# gatorBytes_LED_board.net
KiCad netlist of a schematic drawn in EAGLE
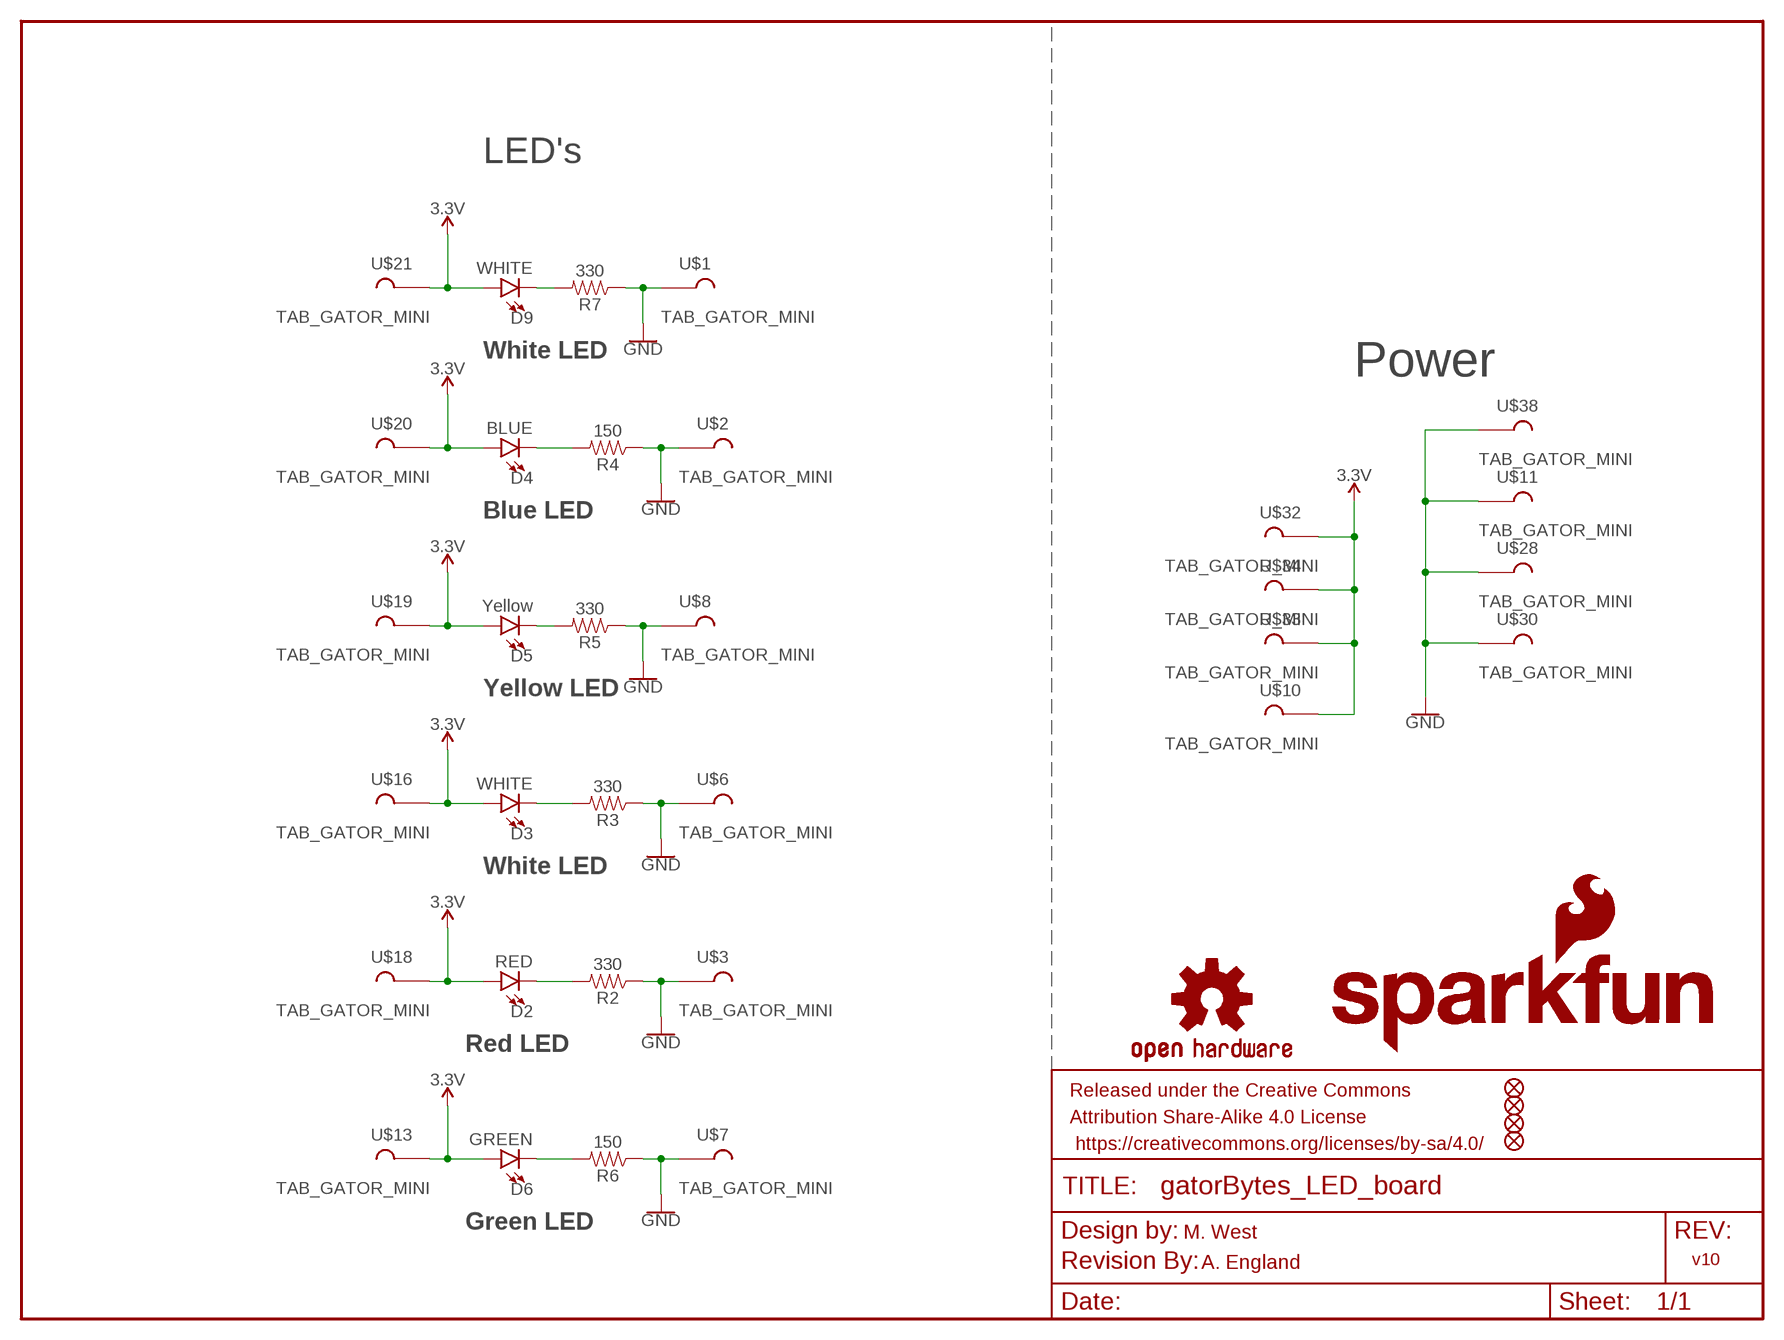
[diagram p0: schematic, sheet 1]

(export (version "E")
  (design (tool "Eeschema 10.0.6"))
  (components
    (comp (ref "D2")
      (value "RED")
      (footprint "eagle-import:LED-1206")
      (libsource (lib "eagle-import") (part "LED-RED1206"))
    )
    (comp (ref "D3")
      (value "WHITE")
      (footprint "eagle-import:LED-1206")
      (libsource (lib "eagle-import") (part "LED-WHITE1206"))
    )
    (comp (ref "D4")
      (value "BLUE")
      (footprint "eagle-import:LED-1206")
      (libsource (lib "eagle-import") (part "LED-BLUE1206"))
    )
    (comp (ref "D5")
      (value "Yellow")
      (footprint "eagle-import:LED-1206")
      (libsource (lib "eagle-import") (part "LED-YELLOWLILYPAD"))
    )
    (comp (ref "D6")
      (value "GREEN")
      (footprint "eagle-import:LED-1206")
      (libsource (lib "eagle-import") (part "LED-GREEN1206"))
    )
    (comp (ref "D9")
      (value "WHITE")
      (footprint "eagle-import:LED-1206")
      (libsource (lib "eagle-import") (part "LED-WHITE1206"))
    )
    (comp (ref "FD1")
      (value "FIDUCIALUFIDUCIAL")
      (footprint "eagle-import:FIDUCIAL-MICRO")
      (libsource (lib "eagle-import") (part "FIDUCIALUFIDUCIAL"))
    )
    (comp (ref "FD2")
      (value "FIDUCIALUFIDUCIAL")
      (footprint "eagle-import:FIDUCIAL-MICRO")
      (libsource (lib "eagle-import") (part "FIDUCIALUFIDUCIAL"))
    )
    (comp (ref "FD3")
      (value "FIDUCIALUFIDUCIAL")
      (footprint "eagle-import:FIDUCIAL-MICRO")
      (libsource (lib "eagle-import") (part "FIDUCIALUFIDUCIAL"))
    )
    (comp (ref "FD4")
      (value "FIDUCIALUFIDUCIAL")
      (footprint "eagle-import:FIDUCIAL-MICRO")
      (libsource (lib "eagle-import") (part "FIDUCIALUFIDUCIAL"))
    )
    (comp (ref "FRAME1")
      (value "FRAME-LETTER")
      (footprint "eagle-import:CREATIVE_COMMONS")
      (libsource (lib "eagle-import") (part "FRAME-LETTER"))
    )
    (comp (ref "LOGO1")
      (value "SFE_LOGO_FLAME.1_INCH")
      (footprint "eagle-import:SFE_LOGO_FLAME_.1")
      (libsource (lib "eagle-import") (part "SFE_LOGO_FLAME.1_INCH"))
    )
    (comp (ref "LOGO2")
      (value "OSHW-LOGOMINI")
      (footprint "eagle-import:OSHW-LOGO-MINI")
      (libsource (lib "eagle-import") (part "OSHW-LOGOMINI"))
    )
    (comp (ref "LOGO8")
      (value "REVISION")
      (footprint "eagle-import:REVISION")
      (libsource (lib "eagle-import") (part "REVISION"))
    )
    (comp (ref "LOGO15")
      (value "OSHW-LOGOMINI")
      (footprint "eagle-import:OSHW-LOGO-MINI")
      (libsource (lib "eagle-import") (part "OSHW-LOGOMINI"))
    )
    (comp (ref "LOGO16")
      (value "SFE_LOGO_NAME.1_INCH")
      (footprint "eagle-import:SFE_LOGO_NAME_.1")
      (libsource (lib "eagle-import") (part "SFE_LOGO_NAME.1_INCH"))
    )
    (comp (ref "R2")
      (value "330")
      (footprint "eagle-import:0603")
      (libsource (lib "eagle-import") (part "330OHM-0603-1/10W-1%"))
    )
    (comp (ref "R3")
      (value "330")
      (footprint "eagle-import:0603")
      (libsource (lib "eagle-import") (part "330OHM-0603-1/10W-1%"))
    )
    (comp (ref "R4")
      (value "150")
      (footprint "eagle-import:0603")
      (libsource (lib "eagle-import") (part "150OHM-0603-1/10W-1%"))
    )
    (comp (ref "R5")
      (value "330")
      (footprint "eagle-import:0603")
      (libsource (lib "eagle-import") (part "330OHM-0603-1/10W-1%"))
    )
    (comp (ref "R6")
      (value "150")
      (footprint "eagle-import:0603")
      (libsource (lib "eagle-import") (part "150OHM-0603-1/10W-1%"))
    )
    (comp (ref "R7")
      (value "330")
      (footprint "eagle-import:0603")
      (libsource (lib "eagle-import") (part "330OHM-0603-1/10W-1%"))
    )
    (comp (ref "U$1")
      (value "TAB_GATOR_MINI")
      (footprint "eagle-import:TAB_GATOR_MINI")
      (libsource (lib "eagle-import") (part "TAB_GATOR_MINI"))
    )
    (comp (ref "U$2")
      (value "TAB_GATOR_MINI")
      (footprint "eagle-import:TAB_GATOR_MINI")
      (libsource (lib "eagle-import") (part "TAB_GATOR_MINI"))
    )
    (comp (ref "U$3")
      (value "TAB_GATOR_MINI")
      (footprint "eagle-import:TAB_GATOR_MINI")
      (libsource (lib "eagle-import") (part "TAB_GATOR_MINI"))
    )
    (comp (ref "U$6")
      (value "TAB_GATOR_MINI")
      (footprint "eagle-import:TAB_GATOR_MINI")
      (libsource (lib "eagle-import") (part "TAB_GATOR_MINI"))
    )
    (comp (ref "U$7")
      (value "TAB_GATOR_MINI")
      (footprint "eagle-import:TAB_GATOR_MINI")
      (libsource (lib "eagle-import") (part "TAB_GATOR_MINI"))
    )
    (comp (ref "U$8")
      (value "TAB_GATOR_MINI")
      (footprint "eagle-import:TAB_GATOR_MINI")
      (libsource (lib "eagle-import") (part "TAB_GATOR_MINI"))
    )
    (comp (ref "U$10")
      (value "TAB_GATOR_MINI")
      (footprint "eagle-import:TAB_GATOR_MINI")
      (libsource (lib "eagle-import") (part "TAB_GATOR_MINI"))
    )
    (comp (ref "U$11")
      (value "TAB_GATOR_MINI")
      (footprint "eagle-import:TAB_GATOR_MINI")
      (libsource (lib "eagle-import") (part "TAB_GATOR_MINI"))
    )
    (comp (ref "U$13")
      (value "TAB_GATOR_MINI")
      (footprint "eagle-import:TAB_GATOR_MINI")
      (libsource (lib "eagle-import") (part "TAB_GATOR_MINI"))
    )
    (comp (ref "U$16")
      (value "TAB_GATOR_MINI")
      (footprint "eagle-import:TAB_GATOR_MINI")
      (libsource (lib "eagle-import") (part "TAB_GATOR_MINI"))
    )
    (comp (ref "U$18")
      (value "TAB_GATOR_MINI")
      (footprint "eagle-import:TAB_GATOR_MINI")
      (libsource (lib "eagle-import") (part "TAB_GATOR_MINI"))
    )
    (comp (ref "U$19")
      (value "TAB_GATOR_MINI")
      (footprint "eagle-import:TAB_GATOR_MINI")
      (libsource (lib "eagle-import") (part "TAB_GATOR_MINI"))
    )
    (comp (ref "U$20")
      (value "TAB_GATOR_MINI")
      (footprint "eagle-import:TAB_GATOR_MINI")
      (libsource (lib "eagle-import") (part "TAB_GATOR_MINI"))
    )
    (comp (ref "U$21")
      (value "TAB_GATOR_MINI")
      (footprint "eagle-import:TAB_GATOR_MINI")
      (libsource (lib "eagle-import") (part "TAB_GATOR_MINI"))
    )
    (comp (ref "U$28")
      (value "TAB_GATOR_MINI")
      (footprint "eagle-import:TAB_GATOR_MINI")
      (libsource (lib "eagle-import") (part "TAB_GATOR_MINI"))
    )
    (comp (ref "U$30")
      (value "TAB_GATOR_MINI")
      (footprint "eagle-import:TAB_GATOR_MINI")
      (libsource (lib "eagle-import") (part "TAB_GATOR_MINI"))
    )
    (comp (ref "U$32")
      (value "TAB_GATOR_MINI")
      (footprint "eagle-import:TAB_GATOR_MINI")
      (libsource (lib "eagle-import") (part "TAB_GATOR_MINI"))
    )
    (comp (ref "U$33")
      (value "TAB_GATOR_MINI")
      (footprint "eagle-import:TAB_GATOR_MINI")
      (libsource (lib "eagle-import") (part "TAB_GATOR_MINI"))
    )
    (comp (ref "U$34")
      (value "TAB_GATOR_MINI")
      (footprint "eagle-import:TAB_GATOR_MINI")
      (libsource (lib "eagle-import") (part "TAB_GATOR_MINI"))
    )
    (comp (ref "U$38")
      (value "TAB_GATOR_MINI")
      (footprint "eagle-import:TAB_GATOR_MINI")
      (libsource (lib "eagle-import") (part "TAB_GATOR_MINI"))
    )
  )
  (nets
    (net (code "1") (name "3.3V") (class "Default")
      (node (ref "D2") (pin "A") (pinfunction "A_A") (pintype "passive"))
      (node (ref "D3") (pin "A") (pinfunction "A_A") (pintype "passive"))
      (node (ref "D4") (pin "A") (pinfunction "A_A") (pintype "passive"))
      (node (ref "D5") (pin "A") (pinfunction "A_A") (pintype "passive"))
      (node (ref "D6") (pin "A") (pinfunction "A_A") (pintype "passive"))
      (node (ref "D9") (pin "A") (pinfunction "A_A") (pintype "passive"))
      (node (ref "U$10") (pin "P1") (pinfunction "P$1_P1") (pintype "bidirectional"))
      (node (ref "U$13") (pin "P1") (pinfunction "P$1_P1") (pintype "bidirectional"))
      (node (ref "U$16") (pin "P1") (pinfunction "P$1_P1") (pintype "bidirectional"))
      (node (ref "U$18") (pin "P1") (pinfunction "P$1_P1") (pintype "bidirectional"))
      (node (ref "U$19") (pin "P1") (pinfunction "P$1_P1") (pintype "bidirectional"))
      (node (ref "U$20") (pin "P1") (pinfunction "P$1_P1") (pintype "bidirectional"))
      (node (ref "U$21") (pin "P1") (pinfunction "P$1_P1") (pintype "bidirectional"))
      (node (ref "U$32") (pin "P1") (pinfunction "P$1_P1") (pintype "bidirectional"))
      (node (ref "U$33") (pin "P1") (pinfunction "P$1_P1") (pintype "bidirectional"))
      (node (ref "U$34") (pin "P1") (pinfunction "P$1_P1") (pintype "bidirectional"))
    )
    (net (code "2") (name "GND") (class "Default")
      (node (ref "R2") (pin "1") (pinfunction "1_1") (pintype "passive"))
      (node (ref "R3") (pin "1") (pinfunction "1_1") (pintype "passive"))
      (node (ref "R4") (pin "1") (pinfunction "1_1") (pintype "passive"))
      (node (ref "R5") (pin "1") (pinfunction "1_1") (pintype "passive"))
      (node (ref "R6") (pin "1") (pinfunction "1_1") (pintype "passive"))
      (node (ref "R7") (pin "1") (pinfunction "1_1") (pintype "passive"))
      (node (ref "U$1") (pin "P1") (pinfunction "P$1_P1") (pintype "bidirectional"))
      (node (ref "U$11") (pin "P1") (pinfunction "P$1_P1") (pintype "bidirectional"))
      (node (ref "U$2") (pin "P1") (pinfunction "P$1_P1") (pintype "bidirectional"))
      (node (ref "U$28") (pin "P1") (pinfunction "P$1_P1") (pintype "bidirectional"))
      (node (ref "U$3") (pin "P1") (pinfunction "P$1_P1") (pintype "bidirectional"))
      (node (ref "U$30") (pin "P1") (pinfunction "P$1_P1") (pintype "bidirectional"))
      (node (ref "U$38") (pin "P1") (pinfunction "P$1_P1") (pintype "bidirectional"))
      (node (ref "U$6") (pin "P1") (pinfunction "P$1_P1") (pintype "bidirectional"))
      (node (ref "U$7") (pin "P1") (pinfunction "P$1_P1") (pintype "bidirectional"))
      (node (ref "U$8") (pin "P1") (pinfunction "P$1_P1") (pintype "bidirectional"))
    )
    (net (code "3") (name "Net-(D2-PadC)") (class "Default")
      (node (ref "D2") (pin "C") (pinfunction "C_C") (pintype "passive"))
      (node (ref "R2") (pin "2") (pinfunction "2_2") (pintype "passive"))
    )
    (net (code "4") (name "Net-(D3-PadC)") (class "Default")
      (node (ref "D3") (pin "C") (pinfunction "C_C") (pintype "passive"))
      (node (ref "R3") (pin "2") (pinfunction "2_2") (pintype "passive"))
    )
    (net (code "5") (name "Net-(D4-PadC)") (class "Default")
      (node (ref "D4") (pin "C") (pinfunction "C_C") (pintype "passive"))
      (node (ref "R4") (pin "2") (pinfunction "2_2") (pintype "passive"))
    )
    (net (code "6") (name "Net-(D5-PadC)") (class "Default")
      (node (ref "D5") (pin "C") (pinfunction "C_C") (pintype "passive"))
      (node (ref "R5") (pin "2") (pinfunction "2_2") (pintype "passive"))
    )
    (net (code "7") (name "Net-(D6-PadC)") (class "Default")
      (node (ref "D6") (pin "C") (pinfunction "C_C") (pintype "passive"))
      (node (ref "R6") (pin "2") (pinfunction "2_2") (pintype "passive"))
    )
    (net (code "8") (name "Net-(D9-PadC)") (class "Default")
      (node (ref "D9") (pin "C") (pinfunction "C_C") (pintype "passive"))
      (node (ref "R7") (pin "2") (pinfunction "2_2") (pintype "passive"))
    )
  )
)
